# cpu.net
KiCad netlist of a schematic drawn in Altium Designer
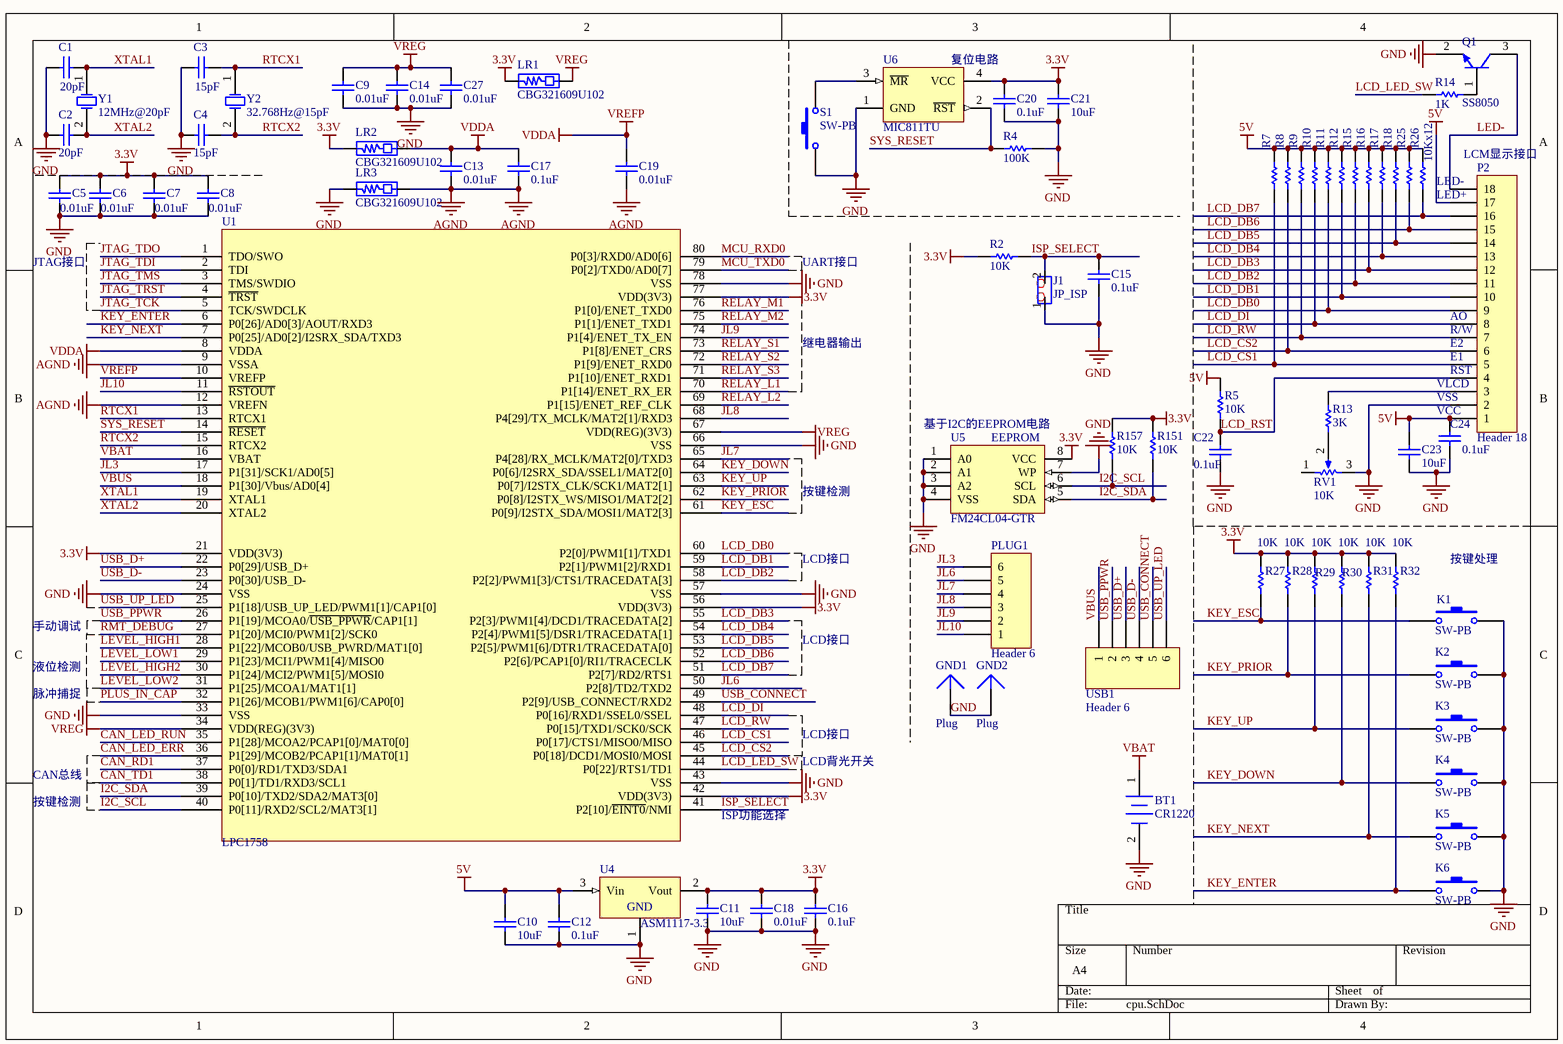
[diagram p0: cpu.SchDoc]

(export (version "E")
  (design (tool "Eeschema 10.0.6"))
  (components
    (comp (ref "BT1")
      (value "CR1220")
      (footprint "BAT-CR1220A")
      (description "Battery holder")
      (fields (field (name "PUBLISHER") "Altium Limited"))
      (libsource (lib "Miscellaneous Devices") (part "Battery"))
    )
    (comp (ref "C1")
      (value "20pF")
      (footprint "CAPC2012M")
      (description "Capacitor")
      (fields (field (name "PUBLISHER") "Altium Limited"))
      (libsource (lib "Miscellaneous Devices") (part "Cap"))
    )
    (comp (ref "C2")
      (value "20pF")
      (footprint "CAPC2012M")
      (description "Capacitor")
      (fields (field (name "PUBLISHER") "Altium Limited"))
      (libsource (lib "Miscellaneous Devices") (part "Cap"))
    )
    (comp (ref "C3")
      (value "15pF")
      (footprint "CAPC2012M")
      (description "Capacitor")
      (fields (field (name "PUBLISHER") "Altium Limited"))
      (libsource (lib "Miscellaneous Devices") (part "Cap"))
    )
    (comp (ref "C4")
      (value "15pF")
      (footprint "CAPC2012M")
      (description "Capacitor")
      (fields (field (name "PUBLISHER") "Altium Limited"))
      (libsource (lib "Miscellaneous Devices") (part "Cap"))
    )
    (comp (ref "C5")
      (value "0.01uF")
      (footprint "CAPC2012M")
      (description "Capacitor")
      (fields (field (name "PUBLISHER") "Altium Limited"))
      (libsource (lib "Miscellaneous Devices") (part "Cap"))
    )
    (comp (ref "C6")
      (value "0.01uF")
      (footprint "CAPC2012M")
      (description "Capacitor")
      (fields (field (name "PUBLISHER") "Altium Limited"))
      (libsource (lib "Miscellaneous Devices") (part "Cap"))
    )
    (comp (ref "C7")
      (value "0.01uF")
      (footprint "CAPC2012M")
      (description "Capacitor")
      (fields (field (name "PUBLISHER") "Altium Limited"))
      (libsource (lib "Miscellaneous Devices") (part "Cap"))
    )
    (comp (ref "C8")
      (value "0.01uF")
      (footprint "CAPC2012M")
      (description "Capacitor")
      (fields (field (name "PUBLISHER") "Altium Limited"))
      (libsource (lib "Miscellaneous Devices") (part "Cap"))
    )
    (comp (ref "C9")
      (value "0.01uF")
      (footprint "CAPC2012M")
      (description "Capacitor")
      (fields (field (name "PUBLISHER") "Altium Limited"))
      (libsource (lib "Miscellaneous Devices") (part "Cap"))
    )
    (comp (ref "C10")
      (value "10uF")
      (footprint "CAPC2012M")
      (description "Capacitor")
      (fields (field (name "PUBLISHER") "Altium Limited"))
      (libsource (lib "Miscellaneous Devices") (part "Cap"))
    )
    (comp (ref "C11")
      (value "10uF")
      (footprint "CAPC2012M")
      (description "Capacitor")
      (fields (field (name "PUBLISHER") "Altium Limited"))
      (libsource (lib "Miscellaneous Devices") (part "Cap"))
    )
    (comp (ref "C12")
      (value "0.1uF")
      (footprint "CAPC2012M")
      (description "Capacitor")
      (fields (field (name "PUBLISHER") "Altium Limited"))
      (libsource (lib "Miscellaneous Devices") (part "Cap"))
    )
    (comp (ref "C13")
      (value "0.01uF")
      (footprint "CAPC2012M")
      (description "Capacitor")
      (fields (field (name "PUBLISHER") "Altium Limited"))
      (libsource (lib "Miscellaneous Devices") (part "Cap"))
    )
    (comp (ref "C14")
      (value "0.01uF")
      (footprint "CAPC2012M")
      (description "Capacitor")
      (fields (field (name "PUBLISHER") "Altium Limited"))
      (libsource (lib "Miscellaneous Devices") (part "Cap"))
    )
    (comp (ref "C15")
      (value "0.1uF")
      (footprint "CAPC2012M")
      (description "Capacitor")
      (fields (field (name "PUBLISHER") "Altium Limited"))
      (libsource (lib "Miscellaneous Devices") (part "Cap"))
    )
    (comp (ref "C16")
      (value "0.1uF")
      (footprint "CAPC2012M")
      (description "Capacitor")
      (fields (field (name "PUBLISHER") "Altium Limited"))
      (libsource (lib "Miscellaneous Devices") (part "Cap"))
    )
    (comp (ref "C17")
      (value "0.1uF")
      (footprint "CAPC2012M")
      (description "Capacitor")
      (fields (field (name "PUBLISHER") "Altium Limited"))
      (libsource (lib "Miscellaneous Devices") (part "Cap"))
    )
    (comp (ref "C18")
      (value "0.01uF")
      (footprint "CAPC2012M")
      (description "Capacitor")
      (fields (field (name "PUBLISHER") "Altium Limited"))
      (libsource (lib "Miscellaneous Devices") (part "Cap"))
    )
    (comp (ref "C19")
      (value "0.01uF")
      (footprint "CAPC2012M")
      (description "Capacitor")
      (fields (field (name "PUBLISHER") "Altium Limited"))
      (libsource (lib "Miscellaneous Devices") (part "Cap"))
    )
    (comp (ref "C20")
      (value "0.1uF")
      (footprint "CAPC2012M")
      (description "Capacitor")
      (fields (field (name "PUBLISHER") "Altium Limited"))
      (libsource (lib "Miscellaneous Devices") (part "Cap"))
    )
    (comp (ref "C21")
      (value "10uF")
      (footprint "CAPC2012M")
      (description "Capacitor")
      (fields (field (name "PUBLISHER") "Altium Limited"))
      (libsource (lib "Miscellaneous Devices") (part "Cap"))
    )
    (comp (ref "C22")
      (value "0.1uF")
      (footprint "CAPC2012M")
      (description "Capacitor")
      (fields (field (name "PUBLISHER") "Altium Limited"))
      (libsource (lib "Miscellaneous Devices") (part "Cap"))
    )
    (comp (ref "C23")
      (value "10uF")
      (footprint "CAPC2012M")
      (description "Capacitor")
      (fields (field (name "PUBLISHER") "Altium Limited"))
      (libsource (lib "Miscellaneous Devices") (part "Cap"))
    )
    (comp (ref "C24")
      (value "0.1uF")
      (footprint "CAPC2012M")
      (description "Capacitor")
      (fields (field (name "PUBLISHER") "Altium Limited"))
      (libsource (lib "Miscellaneous Devices") (part "Cap"))
    )
    (comp (ref "C27")
      (value "0.01uF")
      (footprint "CAPC2012M")
      (description "Capacitor")
      (fields (field (name "PUBLISHER") "Altium Limited"))
      (libsource (lib "Miscellaneous Devices") (part "Cap"))
    )
    (comp (ref "GND1")
      (value "Plug")
      (footprint "PIN1")
      (fields (field (name "PUBLISHER") "Altium Limited"))
      (libsource (lib "Miscellaneous Connectors") (part "Plug"))
    )
    (comp (ref "GND2")
      (value "Plug")
      (footprint "PIN1")
      (fields (field (name "PUBLISHER") "Altium Limited"))
      (libsource (lib "Miscellaneous Connectors") (part "Plug"))
    )
    (comp (ref "J1")
      (value "JP_ISP")
      (footprint "DS-01")
      (description "Dial Switch pitch 7.62mm")
      (libsource (lib "UserLib") (part "JK2H"))
    )
    (comp (ref "K1")
      (value "SW-PB")
      (footprint "PBST-4S")
      (description "Push Button ,6mm(L)x6mm(W)x22mm(H)")
      (fields (field (name "PUBLISHER") "Altium Limited"))
      (libsource (lib "Miscellaneous Devices") (part "SW-PB"))
    )
    (comp (ref "K2")
      (value "SW-PB")
      (footprint "PBST-4S")
      (description "Push Button ,6mm(L)x6mm(W)x22mm(H)")
      (fields (field (name "PUBLISHER") "Altium Limited"))
      (libsource (lib "Miscellaneous Devices") (part "SW-PB"))
    )
    (comp (ref "K3")
      (value "SW-PB")
      (footprint "PBST-4S")
      (description "Push Button ,6mm(L)x6mm(W)x22mm(H)")
      (fields (field (name "PUBLISHER") "Altium Limited"))
      (libsource (lib "Miscellaneous Devices") (part "SW-PB"))
    )
    (comp (ref "K4")
      (value "SW-PB")
      (footprint "PBST-4S")
      (description "Push Button ,6mm(L)x6mm(W)x22mm(H)")
      (fields (field (name "PUBLISHER") "Altium Limited"))
      (libsource (lib "Miscellaneous Devices") (part "SW-PB"))
    )
    (comp (ref "K5")
      (value "SW-PB")
      (footprint "PBST-4S")
      (description "Push Button ,6mm(L)x6mm(W)x22mm(H)")
      (fields (field (name "PUBLISHER") "Altium Limited"))
      (libsource (lib "Miscellaneous Devices") (part "SW-PB"))
    )
    (comp (ref "K6")
      (value "SW-PB")
      (footprint "PBST-4S")
      (description "Push Button ,6mm(L)x6mm(W)x22mm(H)")
      (fields (field (name "PUBLISHER") "Altium Limited"))
      (libsource (lib "Miscellaneous Devices") (part "SW-PB"))
    )
    (comp (ref "LR1")
      (value "CBG321609U102")
      (footprint "RESC3216M")
      (description "EMI FILTERS,DC Resistance max.0.05~1.5 ohms,10 ~ 1000 ohms at 100MHz  Frequency")
      (libsource (lib "UserLib") (part "BLM10/11/21/31/41"))
    )
    (comp (ref "LR2")
      (value "CBG321609U102")
      (footprint "RESC3216M")
      (description "EMI FILTERS,DC Resistance max.0.05~1.5 ohms,10 ~ 1000 ohms at 100MHz  Frequency")
      (libsource (lib "UserLib") (part "BLM10/11/21/31/41"))
    )
    (comp (ref "LR3")
      (value "CBG321609U102")
      (footprint "RESC3216M")
      (description "EMI FILTERS,DC Resistance max.0.05~1.5 ohms,10 ~ 1000 ohms at 100MHz  Frequency")
      (libsource (lib "UserLib") (part "BLM10/11/21/31/41"))
    )
    (comp (ref "P2")
      (value "Header 18")
      (footprint "HDR1X18")
      (description "'Female Header,Single Row Straight, 20-Pin,Pitch 2.54mm,black")
      (fields (field (name "PUBLISHER") "Altium Limited"))
      (libsource (lib "Miscellaneous Connectors") (part "Header 18H"))
    )
    (comp (ref "PLUG1")
      (value "Header 6")
      (footprint "HDR1X6")
      (description "Header, 6-Pin")
      (fields (field (name "PUBLISHER") "Altium Limited"))
      (libsource (lib "Miscellaneous Connectors") (part "Header 6"))
    )
    (comp (ref "Q1")
      (value "SS8050")
      (footprint "SOT-23_N")
      (description "NPN BISS Transistor")
      (fields (field (name "PUBLISHER") "Altium Limited"))
      (libsource (lib "Philips Discrete BJT - Low Power") (part "PMMT491A"))
    )
    (comp (ref "R2")
      (value "10K")
      (footprint "RESC2012M")
      (description "Resistor")
      (fields (field (name "PUBLISHER") "Altium Limited"))
      (libsource (lib "Miscellaneous Devices") (part "Res1"))
    )
    (comp (ref "R4")
      (value "100K")
      (footprint "RESC2012M")
      (description "Resistor")
      (fields (field (name "PUBLISHER") "Altium Limited"))
      (libsource (lib "Miscellaneous Devices") (part "Res1"))
    )
    (comp (ref "R5")
      (value "10K")
      (footprint "RESC2012M")
      (description "Resistor")
      (fields (field (name "PUBLISHER") "Altium Limited"))
      (libsource (lib "Miscellaneous Devices") (part "Res1"))
    )
    (comp (ref "R7")
      (value "10K")
      (footprint "RESC2012M")
      (description "Resistor")
      (fields (field (name "PUBLISHER") "Altium Limited"))
      (libsource (lib "Miscellaneous Devices") (part "Res1"))
    )
    (comp (ref "R8")
      (value "10K")
      (footprint "RESC2012M")
      (description "Resistor")
      (fields (field (name "PUBLISHER") "Altium Limited"))
      (libsource (lib "Miscellaneous Devices") (part "Res1"))
    )
    (comp (ref "R9")
      (value "10K")
      (footprint "RESC2012M")
      (description "Resistor")
      (fields (field (name "PUBLISHER") "Altium Limited"))
      (libsource (lib "Miscellaneous Devices") (part "Res1"))
    )
    (comp (ref "R10")
      (value "10K")
      (footprint "RESC2012M")
      (description "Resistor")
      (fields (field (name "PUBLISHER") "Altium Limited"))
      (libsource (lib "Miscellaneous Devices") (part "Res1"))
    )
    (comp (ref "R11")
      (value "10K")
      (footprint "RESC2012M")
      (description "Resistor")
      (fields (field (name "PUBLISHER") "Altium Limited"))
      (libsource (lib "Miscellaneous Devices") (part "Res1"))
    )
    (comp (ref "R12")
      (value "10K")
      (footprint "RESC2012M")
      (description "Resistor")
      (fields (field (name "PUBLISHER") "Altium Limited"))
      (libsource (lib "Miscellaneous Devices") (part "Res1"))
    )
    (comp (ref "R13")
      (value "3K")
      (footprint "RESC2012M")
      (description "Resistor")
      (fields (field (name "PUBLISHER") "Altium Limited"))
      (libsource (lib "Miscellaneous Devices") (part "Res1"))
    )
    (comp (ref "R14")
      (value "1K")
      (footprint "RESC2012M")
      (description "Resistor")
      (fields (field (name "PUBLISHER") "Altium Limited"))
      (libsource (lib "Miscellaneous Devices") (part "Res1"))
    )
    (comp (ref "R15")
      (value "10K")
      (footprint "RESC2012M")
      (description "Resistor")
      (fields (field (name "PUBLISHER") "Altium Limited"))
      (libsource (lib "Miscellaneous Devices") (part "Res1"))
    )
    (comp (ref "R16")
      (value "10K")
      (footprint "RESC2012M")
      (description "Resistor")
      (fields (field (name "PUBLISHER") "Altium Limited"))
      (libsource (lib "Miscellaneous Devices") (part "Res1"))
    )
    (comp (ref "R17")
      (value "10K")
      (footprint "RESC2012M")
      (description "Resistor")
      (fields (field (name "PUBLISHER") "Altium Limited"))
      (libsource (lib "Miscellaneous Devices") (part "Res1"))
    )
    (comp (ref "R18")
      (value "10K")
      (footprint "RESC2012M")
      (description "Resistor")
      (fields (field (name "PUBLISHER") "Altium Limited"))
      (libsource (lib "Miscellaneous Devices") (part "Res1"))
    )
    (comp (ref "R25")
      (value "10K")
      (footprint "RESC2012M")
      (description "Resistor")
      (fields (field (name "PUBLISHER") "Altium Limited"))
      (libsource (lib "Miscellaneous Devices") (part "Res1"))
    )
    (comp (ref "R26")
      (value "10K")
      (footprint "RESC2012M")
      (description "Resistor")
      (fields (field (name "PUBLISHER") "Altium Limited"))
      (libsource (lib "Miscellaneous Devices") (part "Res1"))
    )
    (comp (ref "R27")
      (value "10K")
      (footprint "RESC2012M")
      (description "Resistor")
      (fields (field (name "PUBLISHER") "Altium Limited"))
      (libsource (lib "Miscellaneous Devices") (part "Res1"))
    )
    (comp (ref "R28")
      (value "10K")
      (footprint "RESC2012M")
      (description "Resistor")
      (fields (field (name "PUBLISHER") "Altium Limited"))
      (libsource (lib "Miscellaneous Devices") (part "Res1"))
    )
    (comp (ref "R29")
      (value "10K")
      (footprint "RESC2012M")
      (description "Resistor")
      (fields (field (name "PUBLISHER") "Altium Limited"))
      (libsource (lib "Miscellaneous Devices") (part "Res1"))
    )
    (comp (ref "R30")
      (value "10K")
      (footprint "RESC2012M")
      (description "Resistor")
      (fields (field (name "PUBLISHER") "Altium Limited"))
      (libsource (lib "Miscellaneous Devices") (part "Res1"))
    )
    (comp (ref "R31")
      (value "10K")
      (footprint "RESC2012M")
      (description "Resistor")
      (fields (field (name "PUBLISHER") "Altium Limited"))
      (libsource (lib "Miscellaneous Devices") (part "Res1"))
    )
    (comp (ref "R32")
      (value "10K")
      (footprint "RESC2012M")
      (description "Resistor")
      (fields (field (name "PUBLISHER") "Altium Limited"))
      (libsource (lib "Miscellaneous Devices") (part "Res1"))
    )
    (comp (ref "R151")
      (value "10K")
      (footprint "RESC2012M")
      (description "Resistor")
      (fields (field (name "PUBLISHER") "Altium Limited"))
      (libsource (lib "Miscellaneous Devices") (part "Res1"))
    )
    (comp (ref "R157")
      (value "10K")
      (footprint "RESC2012M")
      (description "Resistor")
      (fields (field (name "PUBLISHER") "Altium Limited"))
      (libsource (lib "Miscellaneous Devices") (part "Res1"))
    )
    (comp (ref "RV1")
      (value "10K")
      (footprint "VR5S")
      (description "Potentiometer")
      (fields (field (name "PUBLISHER") "Altium Limited"))
      (libsource (lib "UserLib") (part "RPot-A"))
    )
    (comp (ref "S1")
      (value "SW-PB")
      (footprint "DPST-4S")
      (description "Push Button ,2mm(L)x2mm(W)x10mm(H)")
      (fields (field (name "PUBLISHER") "Altium Limited"))
      (libsource (lib "Miscellaneous Devices") (part "SW-PB"))
    )
    (comp (ref "U1") (value "LPC1758") (footprint "LQFP80_M") (libsource (lib "UserLib") (part "LPC1758")))
    (comp (ref "U4")
      (value "ASM1117-3.3")
      (footprint "SOT-223")
      (description "800mA Low-Dropout Linear Regulator")
      (libsource (lib "UserLib") (part "LM1117T-5.0"))
    )
    (comp (ref "U5")
      (value "FM24CL04-GTR")
      (footprint "SO-8")
      (description "Serial EEPROM")
      (libsource (lib "UserLib") (part "CAT24W02"))
    )
    (comp (ref "U6")
      (value "MIC811TU")
      (footprint "SOT143_N")
      (description "4-Pin 礟 Voltage Monitors with Manual Reset Input")
      (fields (field (name "PUBLISHER") "Altium Limited"))
      (libsource (lib "Maxim Power Mgt Supervisory Circuit") (part "MAX811-EUS-T"))
    )
    (comp (ref "USB1")
      (value "Header 6")
      (footprint "HDR1X6")
      (description "Header, 6-Pin")
      (fields (field (name "PUBLISHER") "Altium Limited"))
      (libsource (lib "") (part "Header 6_1"))
    )
    (comp (ref "Y1")
      (value "12MHz@20pF")
      (footprint "HC_SOC")
      (description "Crystal Oscillator")
      (fields (field (name "PUBLISHER") "Altium Limited"))
      (libsource (lib "Miscellaneous Devices") (part "XTAL"))
    )
    (comp (ref "Y2")
      (value "32.768Hz@15pF")
      (footprint "HC-RTC")
      (description "Crystal Oscillator")
      (fields (field (name "PUBLISHER") "Altium Limited"))
      (libsource (lib "Miscellaneous Devices") (part "XTAL"))
    )
  )
  (nets
    (net (code "1") (name "/CAN_LED_ERR") (class "Default")
      (node (ref "U1") (pin "36") (pinfunction "P1[29]/MCOB2/PCAP1[1]/MAT0[1]_36") (pintype "passive"))
    )
    (net (code "2") (name "/CAN_LED_RUN") (class "Default")
      (node (ref "U1") (pin "35") (pinfunction "P1[28]/MCOA2/PCAP1[0]/MAT0[0]_35") (pintype "passive"))
    )
    (net (code "3") (name "/CAN_RD1") (class "Default")
      (node (ref "U1") (pin "37") (pinfunction "P0[0]/RD1/TXD3/SDA1_37") (pintype "passive"))
    )
    (net (code "4") (name "/CAN_TD1") (class "Default")
      (node (ref "U1") (pin "38") (pinfunction "P0[1]/TD1/RXD3/SCL1_38") (pintype "passive"))
    )
    (net (code "5") (name "/I2C_SCL") (class "Default")
      (node (ref "R157") (pin "2") (pinfunction "2_2") (pintype "passive"))
      (node (ref "U1") (pin "40") (pinfunction "P0[11]/RXD2/SCL2/MAT3[1]_40") (pintype "passive"))
      (node (ref "U5") (pin "6") (pinfunction "SCL_6") (pintype "bidirectional"))
    )
    (net (code "6") (name "/I2C_SDA") (class "Default")
      (node (ref "R151") (pin "1") (pinfunction "1_1") (pintype "passive"))
      (node (ref "U1") (pin "39") (pinfunction "P0[10]/TXD2/SDA2/MAT3[0]_39") (pintype "passive"))
      (node (ref "U5") (pin "5") (pinfunction "SDA_5") (pintype "bidirectional"))
    )
    (net (code "7") (name "/ISP_SELECT") (class "Default")
      (node (ref "C15") (pin "1") (pinfunction "1_1") (pintype "passive"))
      (node (ref "J1") (pin "2") (pintype "passive"))
      (node (ref "R2") (pin "2") (pinfunction "2_2") (pintype "passive"))
      (node (ref "U1") (pin "41") (pinfunction "P2[10]/~{EINT0}/NMI_41") (pintype "passive"))
    )
    (net (code "8") (name "/JL3") (class "Default")
      (node (ref "PLUG1") (pin "6") (pinfunction "6_6") (pintype "passive"))
      (node (ref "U1") (pin "17") (pinfunction "P1[31]/SCK1/AD0[5]_17") (pintype "passive"))
    )
    (net (code "9") (name "/JL6") (class "Default")
      (node (ref "PLUG1") (pin "5") (pinfunction "5_5") (pintype "passive"))
      (node (ref "U1") (pin "50") (pinfunction "P2[8]/TD2/TXD2_50") (pintype "passive"))
    )
    (net (code "10") (name "/JL7") (class "Default")
      (node (ref "PLUG1") (pin "4") (pinfunction "4_4") (pintype "passive"))
      (node (ref "U1") (pin "65") (pinfunction "P4[28]/RX_MCLK/MAT2[0]/TXD3_65") (pintype "passive"))
    )
    (net (code "11") (name "/JL8") (class "Default")
      (node (ref "PLUG1") (pin "3") (pinfunction "3_3") (pintype "passive"))
      (node (ref "U1") (pin "68") (pinfunction "P4[29]/TX_MCLK/MAT2[1]/RXD3_68") (pintype "passive"))
    )
    (net (code "12") (name "/JL9") (class "Default")
      (node (ref "PLUG1") (pin "2") (pinfunction "2_2") (pintype "passive"))
      (node (ref "U1") (pin "74") (pinfunction "P1[4]/ENET_TX_EN_74") (pintype "passive"))
    )
    (net (code "13") (name "/JL10") (class "Default")
      (node (ref "PLUG1") (pin "1") (pinfunction "1_1") (pintype "passive"))
      (node (ref "U1") (pin "11") (pinfunction "~{RSTOUT}_11") (pintype "passive"))
    )
    (net (code "14") (name "/JTAG_TCK") (class "Default")
      (node (ref "U1") (pin "5") (pinfunction "TCK/SWDCLK_5") (pintype "passive"))
    )
    (net (code "15") (name "/JTAG_TDI") (class "Default")
      (node (ref "U1") (pin "2") (pinfunction "TDI_2") (pintype "passive"))
    )
    (net (code "16") (name "/JTAG_TDO") (class "Default")
      (node (ref "U1") (pin "1") (pinfunction "TDO/SWO_1") (pintype "passive"))
    )
    (net (code "17") (name "/JTAG_TMS") (class "Default")
      (node (ref "U1") (pin "3") (pinfunction "TMS/SWDIO_3") (pintype "passive"))
    )
    (net (code "18") (name "/JTAG_TRST") (class "Default")
      (node (ref "U1") (pin "4") (pinfunction "~{TRST}_4") (pintype "passive"))
    )
    (net (code "19") (name "/KEY_DOWN") (class "Default")
      (node (ref "K4") (pin "1") (pinfunction "1_1") (pintype "passive"))
      (node (ref "R30") (pin "1") (pinfunction "1_1") (pintype "passive"))
      (node (ref "U1") (pin "64") (pinfunction "P0[6]/I2SRX_SDA/SSEL1/MAT2[0]_64") (pintype "passive"))
    )
    (net (code "20") (name "/KEY_ENTER") (class "Default")
      (node (ref "K6") (pin "1") (pinfunction "1_1") (pintype "passive"))
      (node (ref "R32") (pin "1") (pinfunction "1_1") (pintype "passive"))
      (node (ref "U1") (pin "6") (pinfunction "P0[26]/AD0[3]/AOUT/RXD3_6") (pintype "passive"))
    )
    (net (code "21") (name "/KEY_ESC") (class "Default")
      (node (ref "K1") (pin "1") (pinfunction "1_1") (pintype "passive"))
      (node (ref "R27") (pin "1") (pinfunction "1_1") (pintype "passive"))
      (node (ref "U1") (pin "61") (pinfunction "P0[9]/I2STX_SDA/MOSI1/MAT2[3]_61") (pintype "passive"))
    )
    (net (code "22") (name "/KEY_NEXT") (class "Default")
      (node (ref "K5") (pin "1") (pinfunction "1_1") (pintype "passive"))
      (node (ref "R31") (pin "1") (pinfunction "1_1") (pintype "passive"))
      (node (ref "U1") (pin "7") (pinfunction "P0[25]/AD0[2]/I2SRX_SDA/TXD3_7") (pintype "passive"))
    )
    (net (code "23") (name "/KEY_PRIOR") (class "Default")
      (node (ref "K2") (pin "1") (pinfunction "1_1") (pintype "passive"))
      (node (ref "R28") (pin "1") (pinfunction "1_1") (pintype "passive"))
      (node (ref "U1") (pin "62") (pinfunction "P0[8]/I2STX_WS/MISO1/MAT2[2]_62") (pintype "passive"))
    )
    (net (code "24") (name "/KEY_UP") (class "Default")
      (node (ref "K3") (pin "1") (pinfunction "1_1") (pintype "passive"))
      (node (ref "R29") (pin "1") (pinfunction "1_1") (pintype "passive"))
      (node (ref "U1") (pin "63") (pinfunction "P0[7]/I2STX_CLK/SCK1/MAT2[1]_63") (pintype "passive"))
    )
    (net (code "25") (name "/LCD_CS1") (class "Default")
      (node (ref "P2") (pin "5") (pinfunction "5_5") (pintype "passive"))
      (node (ref "R7") (pin "2") (pinfunction "2_2") (pintype "passive"))
      (node (ref "U1") (pin "46") (pinfunction "P0[17]/CTS1/MISO0/MISO_46") (pintype "passive"))
    )
    (net (code "26") (name "/LCD_CS2") (class "Default")
      (node (ref "P2") (pin "6") (pinfunction "6_6") (pintype "passive"))
      (node (ref "R8") (pin "2") (pinfunction "2_2") (pintype "passive"))
      (node (ref "U1") (pin "45") (pinfunction "P0[18]/DCD1/MOSI0/MOSI_45") (pintype "passive"))
    )
    (net (code "27") (name "/LCD_DB0") (class "Default")
      (node (ref "P2") (pin "9") (pinfunction "9_9") (pintype "passive"))
      (node (ref "R11") (pin "2") (pinfunction "2_2") (pintype "passive"))
      (node (ref "U1") (pin "60") (pinfunction "P2[0]/PWM1[1]/TXD1_60") (pintype "passive"))
    )
    (net (code "28") (name "/LCD_DB1") (class "Default")
      (node (ref "P2") (pin "10") (pinfunction "10_10") (pintype "passive"))
      (node (ref "R12") (pin "2") (pinfunction "2_2") (pintype "passive"))
      (node (ref "U1") (pin "59") (pinfunction "P2[1]/PWM1[2]/RXD1_59") (pintype "passive"))
    )
    (net (code "29") (name "/LCD_DB2") (class "Default")
      (node (ref "P2") (pin "11") (pinfunction "11_11") (pintype "passive"))
      (node (ref "R15") (pin "2") (pinfunction "2_2") (pintype "passive"))
      (node (ref "U1") (pin "58") (pinfunction "P2[2]/PWM1[3]/CTS1/TRACEDATA[3]_58") (pintype "passive"))
    )
    (net (code "30") (name "/LCD_DB3") (class "Default")
      (node (ref "P2") (pin "12") (pinfunction "12_12") (pintype "passive"))
      (node (ref "R16") (pin "2") (pinfunction "2_2") (pintype "passive"))
      (node (ref "U1") (pin "55") (pinfunction "P2[3]/PWM1[4]/DCD1/TRACEDATA[2]_55") (pintype "passive"))
    )
    (net (code "31") (name "/LCD_DB4") (class "Default")
      (node (ref "P2") (pin "13") (pinfunction "13_13") (pintype "passive"))
      (node (ref "R17") (pin "2") (pinfunction "2_2") (pintype "passive"))
      (node (ref "U1") (pin "54") (pinfunction "P2[4]/PWM1[5]/DSR1/TRACEDATA[1]_54") (pintype "passive"))
    )
    (net (code "32") (name "/LCD_DB5") (class "Default")
      (node (ref "P2") (pin "14") (pinfunction "14_14") (pintype "passive"))
      (node (ref "R18") (pin "2") (pinfunction "2_2") (pintype "passive"))
      (node (ref "U1") (pin "53") (pinfunction "P2[5]/PWM1[6]/DTR1/TRACEDATA[0]_53") (pintype "passive"))
    )
    (net (code "33") (name "/LCD_DB6") (class "Default")
      (node (ref "P2") (pin "15") (pinfunction "15_15") (pintype "passive"))
      (node (ref "R25") (pin "2") (pinfunction "2_2") (pintype "passive"))
      (node (ref "U1") (pin "52") (pinfunction "P2[6]/PCAP1[0]/RI1/TRACECLK_52") (pintype "passive"))
    )
    (net (code "34") (name "/LCD_DB7") (class "Default")
      (node (ref "P2") (pin "16") (pinfunction "16_16") (pintype "passive"))
      (node (ref "R26") (pin "2") (pinfunction "2_2") (pintype "passive"))
      (node (ref "U1") (pin "51") (pinfunction "P2[7]/RD2/RTS1_51") (pintype "passive"))
    )
    (net (code "35") (name "/LCD_DI") (class "Default")
      (node (ref "P2") (pin "8") (pinfunction "8_8") (pintype "passive"))
      (node (ref "R10") (pin "2") (pinfunction "2_2") (pintype "passive"))
      (node (ref "U1") (pin "48") (pinfunction "P0[16]/RXD1/SSEL0/SSEL_48") (pintype "passive"))
    )
    (net (code "36") (name "/LCD_LED_SW") (class "Default")
      (node (ref "R14") (pin "1") (pinfunction "1_1") (pintype "passive"))
      (node (ref "U1") (pin "44") (pinfunction "P0[22]/RTS1/TD1_44") (pintype "passive"))
    )
    (net (code "37") (name "/LCD_RST") (class "Default")
      (node (ref "C22") (pin "1") (pinfunction "1_1") (pintype "passive"))
      (node (ref "P2") (pin "4") (pinfunction "4_4") (pintype "passive"))
      (node (ref "R5") (pin "2") (pinfunction "2_2") (pintype "passive"))
    )
    (net (code "38") (name "/LCD_RW") (class "Default")
      (node (ref "P2") (pin "7") (pinfunction "7_7") (pintype "passive"))
      (node (ref "R9") (pin "2") (pinfunction "2_2") (pintype "passive"))
      (node (ref "U1") (pin "47") (pinfunction "P0[15]/TXD1/SCK0/SCK_47") (pintype "passive"))
    )
    (net (code "39") (name "/LED-") (class "Default")
      (node (ref "P2") (pin "18") (pinfunction "18_18") (pintype "passive"))
      (node (ref "Q1") (pin "3") (pinfunction "C_3") (pintype "passive"))
    )
    (net (code "40") (name "/LEVEL_HIGH1") (class "Default")
      (node (ref "U1") (pin "28") (pinfunction "P1[22]/MCOB0/USB_PWRD/MAT1[0]_28") (pintype "passive"))
    )
    (net (code "41") (name "/LEVEL_HIGH2") (class "Default")
      (node (ref "U1") (pin "30") (pinfunction "P1[24]/MCI2/PWM1[5]/MOSI0_30") (pintype "passive"))
    )
    (net (code "42") (name "/LEVEL_LOW1") (class "Default")
      (node (ref "U1") (pin "29") (pinfunction "P1[23]/MCI1/PWM1[4]/MISO0_29") (pintype "passive"))
    )
    (net (code "43") (name "/LEVEL_LOW2") (class "Default")
      (node (ref "U1") (pin "31") (pinfunction "P1[25]/MCOA1/MAT1[1]_31") (pintype "passive"))
    )
    (net (code "44") (name "/MCU_RXD0") (class "Default")
      (node (ref "U1") (pin "80") (pinfunction "P0[3]/RXD0/AD0[6]_80") (pintype "passive"))
    )
    (net (code "45") (name "/MCU_TXD0") (class "Default")
      (node (ref "U1") (pin "79") (pinfunction "P0[2]/TXD0/AD0[7]_79") (pintype "passive"))
    )
    (net (code "46") (name "/PLUS_IN_CAP") (class "Default")
      (node (ref "U1") (pin "32") (pinfunction "P1[26]/MCOB1/PWM1[6]/CAP0[0]_32") (pintype "passive"))
    )
    (net (code "47") (name "/RELAY_L1") (class "Default")
      (node (ref "U1") (pin "70") (pinfunction "P1[14]/ENET_RX_ER_70") (pintype "passive"))
    )
    (net (code "48") (name "/RELAY_L2") (class "Default")
      (node (ref "U1") (pin "69") (pinfunction "P1[15]/ENET_REF_CLK_69") (pintype "passive"))
    )
    (net (code "49") (name "/RELAY_M1") (class "Default")
      (node (ref "U1") (pin "76") (pinfunction "P1[0]/ENET_TXD0_76") (pintype "passive"))
    )
    (net (code "50") (name "/RELAY_M2") (class "Default")
      (node (ref "U1") (pin "75") (pinfunction "P1[1]/ENET_TXD1_75") (pintype "passive"))
    )
    (net (code "51") (name "/RELAY_S1") (class "Default")
      (node (ref "U1") (pin "73") (pinfunction "P1[8]/ENET_CRS_73") (pintype "passive"))
    )
    (net (code "52") (name "/RELAY_S2") (class "Default")
      (node (ref "U1") (pin "72") (pinfunction "P1[9]/ENET_RXD0_72") (pintype "passive"))
    )
    (net (code "53") (name "/RELAY_S3") (class "Default")
      (node (ref "U1") (pin "71") (pinfunction "P1[10]/ENET_RXD1_71") (pintype "passive"))
    )
    (net (code "54") (name "/RMT_DEBUG") (class "Default")
      (node (ref "U1") (pin "27") (pinfunction "P1[20]/MCI0/PWM1[2]/SCK0_27") (pintype "passive"))
    )
    (net (code "55") (name "/RTCX1") (class "Default")
      (node (ref "C3") (pin "1") (pinfunction "1_1") (pintype "passive"))
      (node (ref "U1") (pin "13") (pinfunction "RTCX1_13") (pintype "passive"))
      (node (ref "Y2") (pin "1") (pinfunction "OSC1_1") (pintype "passive"))
    )
    (net (code "56") (name "/RTCX2") (class "Default")
      (node (ref "C4") (pin "1") (pinfunction "1_1") (pintype "passive"))
      (node (ref "U1") (pin "15") (pinfunction "RTCX2_15") (pintype "passive"))
      (node (ref "Y2") (pin "2") (pinfunction "OSC2_2") (pintype "passive"))
    )
    (net (code "57") (name "/SYS_RESET") (class "Default")
      (node (ref "R4") (pin "1") (pinfunction "1_1") (pintype "passive"))
      (node (ref "U1") (pin "14") (pinfunction "~{RESET}_14") (pintype "passive"))
      (node (ref "U6") (pin "2") (pinfunction "~{RST}_2") (pintype "output"))
    )
    (net (code "58") (name "/USB_CONNECT") (class "Default")
      (node (ref "U1") (pin "49") (pinfunction "P2[9]/USB_CONNECT/RXD2_49") (pintype "passive"))
      (node (ref "USB1") (pin "5") (pinfunction "5_5") (pintype "passive"))
    )
    (net (code "59") (name "/USB_D+") (class "Default")
      (node (ref "U1") (pin "22") (pinfunction "P0[29]/USB_D+_22") (pintype "power_in"))
      (node (ref "USB1") (pin "3") (pinfunction "3_3") (pintype "passive"))
    )
    (net (code "60") (name "/USB_D-") (class "Default")
      (node (ref "U1") (pin "23") (pinfunction "P0[30]/USB_D-_23") (pintype "power_in"))
      (node (ref "USB1") (pin "4") (pinfunction "4_4") (pintype "passive"))
    )
    (net (code "61") (name "/USB_PPWR") (class "Default")
      (node (ref "U1") (pin "26") (pinfunction "P1[19]/MCOA0/~{USB_PPWR}/CAP1[1]_26") (pintype "passive"))
      (node (ref "USB1") (pin "2") (pinfunction "2_2") (pintype "passive"))
    )
    (net (code "62") (name "/USB_UP_LED") (class "Default")
      (node (ref "U1") (pin "25") (pinfunction "P1[18]/USB_UP_LED/PWM1[1]/CAP1[0]_25") (pintype "passive"))
      (node (ref "USB1") (pin "6") (pinfunction "6_6") (pintype "passive"))
    )
    (net (code "63") (name "/VBUS") (class "Default")
      (node (ref "U1") (pin "18") (pinfunction "P1[30]/Vbus/AD0[4]_18") (pintype "passive"))
      (node (ref "USB1") (pin "1") (pinfunction "1_1") (pintype "passive"))
    )
    (net (code "64") (name "/XTAL1") (class "Default")
      (node (ref "C1") (pin "1") (pinfunction "1_1") (pintype "passive"))
      (node (ref "U1") (pin "19") (pinfunction "XTAL1_19") (pintype "passive"))
      (node (ref "Y1") (pin "1") (pinfunction "OSC1_1") (pintype "passive"))
    )
    (net (code "65") (name "/XTAL2") (class "Default")
      (node (ref "C2") (pin "1") (pinfunction "1_1") (pintype "passive"))
      (node (ref "U1") (pin "20") (pinfunction "XTAL2_20") (pintype "passive"))
      (node (ref "Y1") (pin "2") (pinfunction "OSC2_2") (pintype "passive"))
    )
    (net (code "66") (name "3.3V") (class "Default")
      (node (ref "C11") (pin "2") (pinfunction "2_2") (pintype "passive"))
      (node (ref "C16") (pin "2") (pinfunction "2_2") (pintype "passive"))
      (node (ref "C18") (pin "2") (pinfunction "2_2") (pintype "passive"))
      (node (ref "C20") (pin "2") (pinfunction "2_2") (pintype "passive"))
      (node (ref "C21") (pin "2") (pinfunction "2_2") (pintype "passive"))
      (node (ref "C5") (pin "2") (pinfunction "2_2") (pintype "passive"))
      (node (ref "C6") (pin "2") (pinfunction "2_2") (pintype "passive"))
      (node (ref "C7") (pin "2") (pinfunction "2_2") (pintype "passive"))
      (node (ref "C8") (pin "2") (pinfunction "2_2") (pintype "passive"))
      (node (ref "LR1") (pin "1") (pinfunction "1_1") (pintype "passive"))
      (node (ref "LR2") (pin "1") (pinfunction "1_1") (pintype "passive"))
      (node (ref "R151") (pin "2") (pinfunction "2_2") (pintype "passive"))
      (node (ref "R157") (pin "1") (pinfunction "1_1") (pintype "passive"))
      (node (ref "R2") (pin "1") (pinfunction "1_1") (pintype "passive"))
      (node (ref "R27") (pin "2") (pinfunction "2_2") (pintype "passive"))
      (node (ref "R28") (pin "2") (pinfunction "2_2") (pintype "passive"))
      (node (ref "R29") (pin "2") (pinfunction "2_2") (pintype "passive"))
      (node (ref "R30") (pin "2") (pinfunction "2_2") (pintype "passive"))
      (node (ref "R31") (pin "2") (pinfunction "2_2") (pintype "passive"))
      (node (ref "R32") (pin "2") (pinfunction "2_2") (pintype "passive"))
      (node (ref "U1") (pin "21") (pinfunction "VDD(3V3)_21") (pintype "power_in"))
      (node (ref "U1") (pin "42") (pinfunction "VDD(3V3)_42") (pintype "passive"))
      (node (ref "U1") (pin "56") (pinfunction "VDD(3V3)_56") (pintype "passive"))
      (node (ref "U1") (pin "77") (pinfunction "VDD(3V3)_77") (pintype "passive"))
      (node (ref "U4") (pin "2") (pinfunction "Vout_2") (pintype "power_in"))
      (node (ref "U5") (pin "8") (pinfunction "VCC_8") (pintype "passive"))
      (node (ref "U6") (pin "4") (pinfunction "VCC_4") (pintype "power_in"))
    )
    (net (code "67") (name "5V") (class "Default")
      (node (ref "C10") (pin "2") (pinfunction "2_2") (pintype "passive"))
      (node (ref "C12") (pin "2") (pinfunction "2_2") (pintype "passive"))
      (node (ref "C23") (pin "2") (pinfunction "2_2") (pintype "passive"))
      (node (ref "C24") (pin "1") (pinfunction "1_1") (pintype "passive"))
      (node (ref "P2") (pin "1") (pinfunction "1_1") (pintype "passive"))
      (node (ref "P2") (pin "17") (pinfunction "17_17") (pintype "passive"))
      (node (ref "R10") (pin "1") (pinfunction "1_1") (pintype "passive"))
      (node (ref "R11") (pin "1") (pinfunction "1_1") (pintype "passive"))
      (node (ref "R12") (pin "1") (pinfunction "1_1") (pintype "passive"))
      (node (ref "R15") (pin "1") (pinfunction "1_1") (pintype "passive"))
      (node (ref "R16") (pin "1") (pinfunction "1_1") (pintype "passive"))
      (node (ref "R17") (pin "1") (pinfunction "1_1") (pintype "passive"))
      (node (ref "R18") (pin "1") (pinfunction "1_1") (pintype "passive"))
      (node (ref "R25") (pin "1") (pinfunction "1_1") (pintype "passive"))
      (node (ref "R26") (pin "1") (pinfunction "1_1") (pintype "passive"))
      (node (ref "R5") (pin "1") (pinfunction "1_1") (pintype "passive"))
      (node (ref "R7") (pin "1") (pinfunction "1_1") (pintype "passive"))
      (node (ref "R8") (pin "1") (pinfunction "1_1") (pintype "passive"))
      (node (ref "R9") (pin "1") (pinfunction "1_1") (pintype "passive"))
      (node (ref "U4") (pin "3") (pinfunction "Vin_3") (pintype "input"))
    )
    (net (code "68") (name "AGND") (class "Default")
      (node (ref "C13") (pin "1") (pinfunction "1_1") (pintype "passive"))
      (node (ref "C17") (pin "1") (pinfunction "1_1") (pintype "passive"))
      (node (ref "C19") (pin "1") (pinfunction "1_1") (pintype "passive"))
      (node (ref "LR3") (pin "2") (pinfunction "2_2") (pintype "passive"))
      (node (ref "U1") (pin "12") (pinfunction "VREFN_12") (pintype "passive"))
      (node (ref "U1") (pin "9") (pinfunction "VSSA_9") (pintype "passive"))
    )
    (net (code "69") (name "GND") (class "Default")
      (node (ref "BT1") (pin "2") (pinfunction "-_2") (pintype "passive"))
      (node (ref "C1") (pin "2") (pinfunction "2_2") (pintype "passive"))
      (node (ref "C10") (pin "1") (pinfunction "1_1") (pintype "passive"))
      (node (ref "C11") (pin "1") (pinfunction "1_1") (pintype "passive"))
      (node (ref "C12") (pin "1") (pinfunction "1_1") (pintype "passive"))
      (node (ref "C14") (pin "1") (pinfunction "1_1") (pintype "passive"))
      (node (ref "C15") (pin "2") (pinfunction "2_2") (pintype "passive"))
      (node (ref "C16") (pin "1") (pinfunction "1_1") (pintype "passive"))
      (node (ref "C18") (pin "1") (pinfunction "1_1") (pintype "passive"))
      (node (ref "C2") (pin "2") (pinfunction "2_2") (pintype "passive"))
      (node (ref "C20") (pin "1") (pinfunction "1_1") (pintype "passive"))
      (node (ref "C21") (pin "1") (pinfunction "1_1") (pintype "passive"))
      (node (ref "C22") (pin "2") (pinfunction "2_2") (pintype "passive"))
      (node (ref "C23") (pin "1") (pinfunction "1_1") (pintype "passive"))
      (node (ref "C24") (pin "2") (pinfunction "2_2") (pintype "passive"))
      (node (ref "C27") (pin "1") (pinfunction "1_1") (pintype "passive"))
      (node (ref "C3") (pin "2") (pinfunction "2_2") (pintype "passive"))
      (node (ref "C4") (pin "2") (pinfunction "2_2") (pintype "passive"))
      (node (ref "C5") (pin "1") (pinfunction "1_1") (pintype "passive"))
      (node (ref "C6") (pin "1") (pinfunction "1_1") (pintype "passive"))
      (node (ref "C7") (pin "1") (pinfunction "1_1") (pintype "passive"))
      (node (ref "C8") (pin "1") (pinfunction "1_1") (pintype "passive"))
      (node (ref "C9") (pin "1") (pinfunction "1_1") (pintype "passive"))
      (node (ref "GND1") (pin "1") (pinfunction "1_1") (pintype "passive"))
      (node (ref "GND2") (pin "1") (pinfunction "1_1") (pintype "passive"))
      (node (ref "J1") (pin "1") (pintype "passive"))
      (node (ref "K1") (pin "2") (pinfunction "2_2") (pintype "passive"))
      (node (ref "K2") (pin "2") (pinfunction "2_2") (pintype "passive"))
      (node (ref "K3") (pin "2") (pinfunction "2_2") (pintype "passive"))
      (node (ref "K4") (pin "2") (pinfunction "2_2") (pintype "passive"))
      (node (ref "K5") (pin "2") (pinfunction "2_2") (pintype "passive"))
      (node (ref "K6") (pin "2") (pinfunction "2_2") (pintype "passive"))
      (node (ref "LR3") (pin "1") (pinfunction "1_1") (pintype "passive"))
      (node (ref "P2") (pin "2") (pinfunction "2_2") (pintype "passive"))
      (node (ref "Q1") (pin "2") (pinfunction "E_2") (pintype "passive"))
      (node (ref "R4") (pin "2") (pinfunction "2_2") (pintype "passive"))
      (node (ref "RV1") (pin "3") (pinfunction "BOT_3") (pintype "passive"))
      (node (ref "S1") (pin "1") (pinfunction "1_1") (pintype "passive"))
      (node (ref "U1") (pin "24") (pinfunction "VSS_24") (pintype "passive"))
      (node (ref "U1") (pin "33") (pinfunction "VSS_33") (pintype "passive"))
      (node (ref "U1") (pin "43") (pinfunction "VSS_43") (pintype "passive"))
      (node (ref "U1") (pin "57") (pinfunction "VSS_57") (pintype "passive"))
      (node (ref "U1") (pin "66") (pinfunction "VSS_66") (pintype "passive"))
      (node (ref "U1") (pin "78") (pinfunction "VSS_78") (pintype "passive"))
      (node (ref "U4") (pin "1") (pinfunction "GND_1") (pintype "passive"))
      (node (ref "U5") (pin "1") (pinfunction "A0_1") (pintype "power_in"))
      (node (ref "U5") (pin "2") (pinfunction "A1_2") (pintype "passive"))
      (node (ref "U5") (pin "3") (pinfunction "A2_3") (pintype "passive"))
      (node (ref "U5") (pin "4") (pinfunction "VSS_4") (pintype "power_in"))
      (node (ref "U5") (pin "7") (pinfunction "WP_7") (pintype "input"))
      (node (ref "U6") (pin "1") (pinfunction "GND_1") (pintype "power_in"))
    )
    (net (code "70") (name "Net-(P2-Pad3)") (class "Default")
      (node (ref "P2") (pin "3") (pinfunction "3_3") (pintype "passive"))
      (node (ref "R13") (pin "2") (pinfunction "2_2") (pintype "passive"))
    )
    (net (code "71") (name "Net-(Q1-B)") (class "Default")
      (node (ref "Q1") (pin "1") (pinfunction "B_1") (pintype "passive"))
      (node (ref "R14") (pin "2") (pinfunction "2_2") (pintype "passive"))
    )
    (net (code "72") (name "Net-(RV1-TAP)") (class "Default")
      (node (ref "R13") (pin "1") (pinfunction "1_1") (pintype "passive"))
      (node (ref "RV1") (pin "2") (pinfunction "TAP_2") (pintype "passive"))
    )
    (net (code "73") (name "Net-(U6-~{MR})") (class "Default")
      (node (ref "S1") (pin "2") (pinfunction "2_2") (pintype "passive"))
      (node (ref "U6") (pin "3") (pinfunction "~{MR}_3") (pintype "input"))
    )
    (net (code "74") (name "VBAT") (class "Default")
      (node (ref "BT1") (pin "1") (pinfunction "+_1") (pintype "passive"))
      (node (ref "U1") (pin "16") (pinfunction "VBAT_16") (pintype "passive"))
    )
    (net (code "75") (name "VDDA") (class "Default")
      (node (ref "C13") (pin "2") (pinfunction "2_2") (pintype "passive"))
      (node (ref "C17") (pin "2") (pinfunction "2_2") (pintype "passive"))
      (node (ref "C19") (pin "2") (pinfunction "2_2") (pintype "passive"))
      (node (ref "LR2") (pin "2") (pinfunction "2_2") (pintype "passive"))
      (node (ref "U1") (pin "10") (pinfunction "VREFP_10") (pintype "passive"))
      (node (ref "U1") (pin "8") (pinfunction "VDDA_8") (pintype "passive"))
    )
    (net (code "76") (name "VREG") (class "Default")
      (node (ref "C14") (pin "2") (pinfunction "2_2") (pintype "passive"))
      (node (ref "C27") (pin "2") (pinfunction "2_2") (pintype "passive"))
      (node (ref "C9") (pin "2") (pinfunction "2_2") (pintype "passive"))
      (node (ref "LR1") (pin "2") (pinfunction "2_2") (pintype "passive"))
      (node (ref "U1") (pin "34") (pinfunction "VDD(REG)(3V3)_34") (pintype "passive"))
      (node (ref "U1") (pin "67") (pinfunction "VDD(REG)(3V3)_67") (pintype "passive"))
    )
    (net (code "77") (name "unconnected-(RV1-TOP-Pad1)") (class "Default")
      (node (ref "RV1") (pin "1") (pinfunction "TOP_1") (pintype "passive"))
    )
  )
)
